# teensy.net
KiCad netlist of a schematic drawn in EAGLE
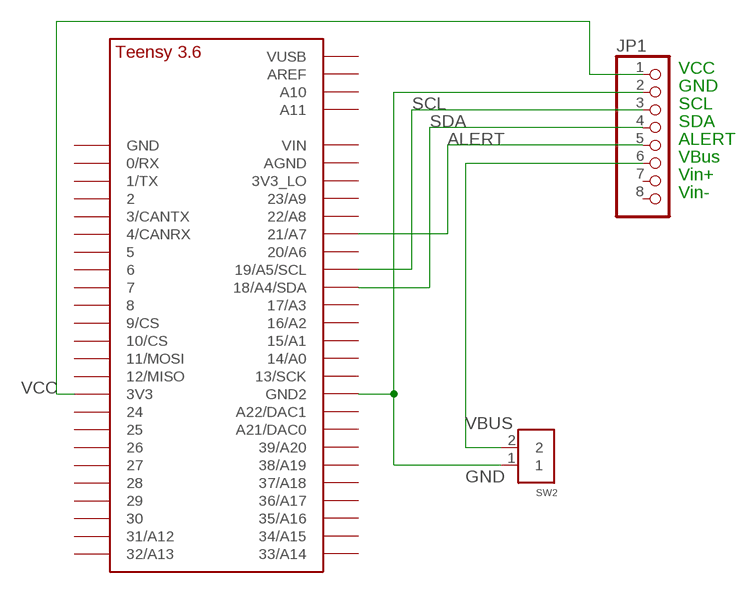
[diagram p0: schematic, sheet 1]

(export (version "E")
  (design (tool "Eeschema 10.0.6"))
  (components
    (comp (ref "JP1")
      (value "PINHD-1X8")
      (footprint "eagle-import:1X08")
      (libsource (lib "eagle-import") (part "PINHD-1X8"))
    )
    (comp (ref "SW2")
      (value "282834-2")
      (footprint "eagle-import:CONN_282834-2")
      (fields (field (name "MF") "TE Connectivity"))
      (libsource (lib "eagle-import") (part "282834-2"))
    )
    (comp (ref "U1")
      (value "TEENSY_3.5/3.6_BASIC")
      (footprint "eagle-import:TEENSY_3.5_3.6_BASIC")
      (libsource (lib "eagle-import") (part "TEENSY_3.5/3.6_BASIC"))
    )
  )
  (nets
    (net (code "1") (name "/ALERT") (class "Default")
      (node (ref "JP1") (pin "5") (pinfunction "5_5") (pintype "passive"))
      (node (ref "U1") (pin "21/A7") (pinfunction "21/A7_21/A7") (pintype "bidirectional"))
    )
    (net (code "2") (name "/GND") (class "Default")
      (node (ref "JP1") (pin "2") (pinfunction "2_2") (pintype "passive"))
      (node (ref "SW2") (pin "1") (pinfunction "1_1") (pintype "passive"))
      (node (ref "U1") (pin "GND2") (pinfunction "GND2_GND2") (pintype "bidirectional"))
    )
    (net (code "3") (name "/SCL") (class "Default")
      (node (ref "JP1") (pin "3") (pinfunction "3_3") (pintype "passive"))
      (node (ref "U1") (pin "19/A5/SCL") (pinfunction "19/A5/SCL_19/A5/SCL") (pintype "bidirectional"))
    )
    (net (code "4") (name "/SDA") (class "Default")
      (node (ref "JP1") (pin "4") (pinfunction "4_4") (pintype "passive"))
      (node (ref "U1") (pin "18/A4/SDA") (pinfunction "18/A4/SDA_18/A4/SDA") (pintype "bidirectional"))
    )
    (net (code "5") (name "/VBUS") (class "Default")
      (node (ref "JP1") (pin "6") (pinfunction "6_6") (pintype "passive"))
      (node (ref "SW2") (pin "2") (pinfunction "2_2") (pintype "passive"))
    )
    (net (code "6") (name "/VCC") (class "Default")
      (node (ref "JP1") (pin "1") (pinfunction "1_1") (pintype "passive"))
      (node (ref "U1") (pin "3V3") (pinfunction "3V3_3V3") (pintype "bidirectional"))
    )
    (net (code "7") (name "unconnected-(JP1-Pad7)") (class "Default")
      (node (ref "JP1") (pin "7") (pinfunction "7_7") (pintype "passive"))
    )
    (net (code "8") (name "unconnected-(JP1-Pad8)") (class "Default")
      (node (ref "JP1") (pin "8") (pinfunction "8_8") (pintype "passive"))
    )
    (net (code "9") (name "unconnected-(U1-A21{slash}DAC0-Pad21{slash}DAC0)") (class "Default")
      (node (ref "U1") (pin "21/DAC0") (pinfunction "A21/DAC0_21/DAC0") (pintype "bidirectional"))
    )
    (net (code "10") (name "unconnected-(U1-Pad0{slash}RX)") (class "Default")
      (node (ref "U1") (pin "0/RX") (pinfunction "0/RX_0/RX") (pintype "bidirectional"))
    )
    (net (code "11") (name "unconnected-(U1-Pad1{slash}TX)") (class "Default")
      (node (ref "U1") (pin "1/TX") (pinfunction "1/TX_1/TX") (pintype "bidirectional"))
    )
    (net (code "12") (name "unconnected-(U1-Pad2)") (class "Default")
      (node (ref "U1") (pin "2") (pinfunction "2_2") (pintype "bidirectional"))
    )
    (net (code "13") (name "unconnected-(U1-Pad3V3_LO)") (class "Default")
      (node (ref "U1") (pin "3V3_LO") (pinfunction "3V3_LO_3V3_LO") (pintype "bidirectional"))
    )
    (net (code "14") (name "unconnected-(U1-Pad3{slash}CANTX)") (class "Default")
      (node (ref "U1") (pin "3/CANTX") (pinfunction "3/CANTX_3/CANTX") (pintype "bidirectional"))
    )
    (net (code "15") (name "unconnected-(U1-Pad4{slash}CANRX)") (class "Default")
      (node (ref "U1") (pin "4/CANRX") (pinfunction "4/CANRX_4/CANRX") (pintype "bidirectional"))
    )
    (net (code "16") (name "unconnected-(U1-Pad5)") (class "Default")
      (node (ref "U1") (pin "5") (pinfunction "5_5") (pintype "bidirectional"))
    )
    (net (code "17") (name "unconnected-(U1-Pad6)") (class "Default")
      (node (ref "U1") (pin "6") (pinfunction "6_6") (pintype "bidirectional"))
    )
    (net (code "18") (name "unconnected-(U1-Pad7)") (class "Default")
      (node (ref "U1") (pin "7") (pinfunction "7_7") (pintype "bidirectional"))
    )
    (net (code "19") (name "unconnected-(U1-Pad8)") (class "Default")
      (node (ref "U1") (pin "8") (pinfunction "8_8") (pintype "bidirectional"))
    )
    (net (code "20") (name "unconnected-(U1-Pad9{slash}CS)") (class "Default")
      (node (ref "U1") (pin "9/CS") (pinfunction "9/CS_9/CS") (pintype "bidirectional"))
    )
    (net (code "21") (name "unconnected-(U1-Pad10{slash}CS)") (class "Default")
      (node (ref "U1") (pin "10/CS") (pinfunction "10/CS_10/CS") (pintype "bidirectional"))
    )
    (net (code "22") (name "unconnected-(U1-Pad11{slash}MOSI)") (class "Default")
      (node (ref "U1") (pin "11/MOSI") (pinfunction "11/MOSI_11/MOSI") (pintype "bidirectional"))
    )
    (net (code "23") (name "unconnected-(U1-Pad12{slash}MISO)") (class "Default")
      (node (ref "U1") (pin "12/MISO") (pinfunction "12/MISO_12/MISO") (pintype "bidirectional"))
    )
    (net (code "24") (name "unconnected-(U1-Pad13{slash}SCK)") (class "Default")
      (node (ref "U1") (pin "13/SCK") (pinfunction "13/SCK_13/SCK") (pintype "bidirectional"))
    )
    (net (code "25") (name "unconnected-(U1-Pad14{slash}A0)") (class "Default")
      (node (ref "U1") (pin "14/A0") (pinfunction "14/A0_14/A0") (pintype "bidirectional"))
    )
    (net (code "26") (name "unconnected-(U1-Pad15{slash}A1)") (class "Default")
      (node (ref "U1") (pin "15/A1") (pinfunction "15/A1_15/A1") (pintype "bidirectional"))
    )
    (net (code "27") (name "unconnected-(U1-Pad16{slash}A2)") (class "Default")
      (node (ref "U1") (pin "16/A2") (pinfunction "16/A2_16/A2") (pintype "bidirectional"))
    )
    (net (code "28") (name "unconnected-(U1-Pad17{slash}A3)") (class "Default")
      (node (ref "U1") (pin "17/A3") (pinfunction "17/A3_17/A3") (pintype "bidirectional"))
    )
    (net (code "29") (name "unconnected-(U1-Pad20{slash}A6)") (class "Default")
      (node (ref "U1") (pin "20/A6") (pinfunction "20/A6_20/A6") (pintype "bidirectional"))
    )
    (net (code "30") (name "unconnected-(U1-Pad22{slash}A8)") (class "Default")
      (node (ref "U1") (pin "22/A8") (pinfunction "22/A8_22/A8") (pintype "bidirectional"))
    )
    (net (code "31") (name "unconnected-(U1-Pad23{slash}A9)") (class "Default")
      (node (ref "U1") (pin "23/A9") (pinfunction "23/A9_23/A9") (pintype "bidirectional"))
    )
    (net (code "32") (name "unconnected-(U1-Pad24)") (class "Default")
      (node (ref "U1") (pin "24") (pinfunction "24_24") (pintype "bidirectional"))
    )
    (net (code "33") (name "unconnected-(U1-Pad25)") (class "Default")
      (node (ref "U1") (pin "25") (pinfunction "25_25") (pintype "bidirectional"))
    )
    (net (code "34") (name "unconnected-(U1-Pad26)") (class "Default")
      (node (ref "U1") (pin "26") (pinfunction "26_26") (pintype "bidirectional"))
    )
    (net (code "35") (name "unconnected-(U1-Pad27)") (class "Default")
      (node (ref "U1") (pin "27") (pinfunction "27_27") (pintype "bidirectional"))
    )
    (net (code "36") (name "unconnected-(U1-Pad28)") (class "Default")
      (node (ref "U1") (pin "28") (pinfunction "28_28") (pintype "bidirectional"))
    )
    (net (code "37") (name "unconnected-(U1-Pad29)") (class "Default")
      (node (ref "U1") (pin "29") (pinfunction "29_29") (pintype "bidirectional"))
    )
    (net (code "38") (name "unconnected-(U1-Pad30)") (class "Default")
      (node (ref "U1") (pin "30") (pinfunction "30_30") (pintype "bidirectional"))
    )
    (net (code "39") (name "unconnected-(U1-Pad31{slash}A12)") (class "Default")
      (node (ref "U1") (pin "31/A12") (pinfunction "31/A12_31/A12") (pintype "bidirectional"))
    )
    (net (code "40") (name "unconnected-(U1-Pad32{slash}A13)") (class "Default")
      (node (ref "U1") (pin "32/A13") (pinfunction "32/A13_32/A13") (pintype "bidirectional"))
    )
    (net (code "41") (name "unconnected-(U1-Pad33{slash}A14)") (class "Default")
      (node (ref "U1") (pin "33/A14") (pinfunction "33/A14_33/A14") (pintype "bidirectional"))
    )
    (net (code "42") (name "unconnected-(U1-Pad34{slash}A15)") (class "Default")
      (node (ref "U1") (pin "34/A15") (pinfunction "34/A15_34/A15") (pintype "bidirectional"))
    )
    (net (code "43") (name "unconnected-(U1-Pad35{slash}A16)") (class "Default")
      (node (ref "U1") (pin "35/A16") (pinfunction "35/A16_35/A16") (pintype "bidirectional"))
    )
    (net (code "44") (name "unconnected-(U1-Pad36{slash}A17)") (class "Default")
      (node (ref "U1") (pin "36/A17") (pinfunction "36/A17_36/A17") (pintype "bidirectional"))
    )
    (net (code "45") (name "unconnected-(U1-Pad37{slash}A18)") (class "Default")
      (node (ref "U1") (pin "37/A18") (pinfunction "37/A18_37/A18") (pintype "bidirectional"))
    )
    (net (code "46") (name "unconnected-(U1-Pad38{slash}A19)") (class "Default")
      (node (ref "U1") (pin "38/A19") (pinfunction "38/A19_38/A19") (pintype "bidirectional"))
    )
    (net (code "47") (name "unconnected-(U1-Pad39{slash}A20)") (class "Default")
      (node (ref "U1") (pin "39/A20") (pinfunction "39/A20_39/A20") (pintype "bidirectional"))
    )
    (net (code "48") (name "unconnected-(U1-PadA10)") (class "Default")
      (node (ref "U1") (pin "A10") (pinfunction "A10_A10") (pintype "bidirectional"))
    )
    (net (code "49") (name "unconnected-(U1-PadA11)") (class "Default")
      (node (ref "U1") (pin "A11") (pinfunction "A11_A11") (pintype "bidirectional"))
    )
    (net (code "50") (name "unconnected-(U1-PadA22{slash}DAC1)") (class "Default")
      (node (ref "U1") (pin "A22/DAC1") (pinfunction "A22/DAC1_A22/DAC1") (pintype "bidirectional"))
    )
    (net (code "51") (name "unconnected-(U1-PadAGND)") (class "Default")
      (node (ref "U1") (pin "AGND") (pinfunction "AGND_AGND") (pintype "bidirectional"))
    )
    (net (code "52") (name "unconnected-(U1-PadAREF)") (class "Default")
      (node (ref "U1") (pin "AREF") (pinfunction "AREF_AREF") (pintype "bidirectional"))
    )
    (net (code "53") (name "unconnected-(U1-PadGND)") (class "Default")
      (node (ref "U1") (pin "GND") (pinfunction "GND_GND") (pintype "bidirectional"))
    )
    (net (code "54") (name "unconnected-(U1-PadVIN)") (class "Default")
      (node (ref "U1") (pin "VIN") (pinfunction "VIN_VIN") (pintype "bidirectional"))
    )
    (net (code "55") (name "unconnected-(U1-PadVUSB)") (class "Default")
      (node (ref "U1") (pin "VUSB") (pinfunction "VUSB_VUSB") (pintype "bidirectional"))
    )
  )
)
